# FPGA_Config.net
KiCad netlist of a schematic drawn in Altium Designer
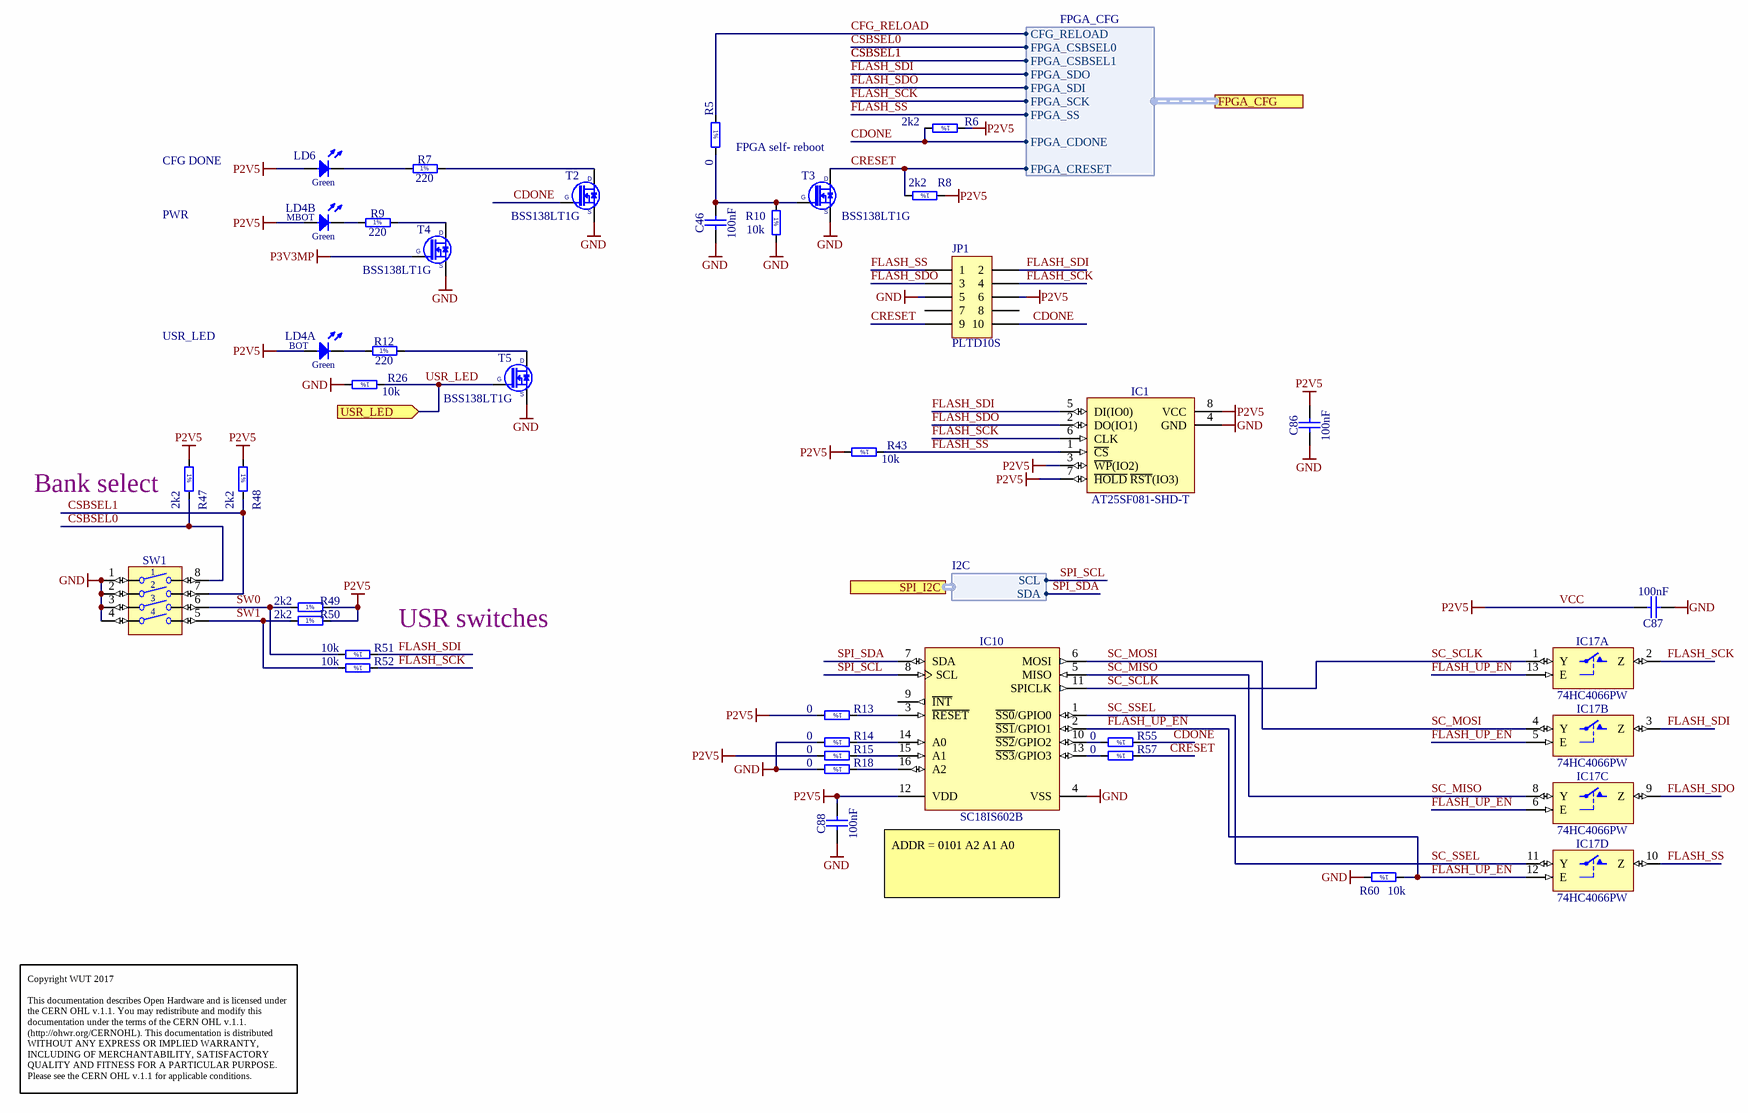
[diagram p0: FPGA_Config.SchDoc]

(export (version "E")
  (design (tool "Eeschema 10.0.6"))
  (components
    (comp (ref "C46")
      (value "100nF")
      (footprint "CAPC1005X55N")
      (description "Non-polarised capacitor")
      (fields
        (field (name "PART NUMBER") "CC0402_100NF_16V_10%_X5R")
        (field (name "VOLTAGE") "16V")
        (field (name "AUTHOR") "CERN DEM JLC")
      )
      (libsource (lib "Capacitors") (part "Capacitor - non polarized"))
    )
    (comp (ref "C86")
      (value "100nF")
      (footprint "CAPC1005X55N")
      (description "Non-polarised capacitor")
      (fields
        (field (name "PART NUMBER") "CC0402_100NF_16V_10%_X5R")
        (field (name "VOLTAGE") "16V")
        (field (name "AUTHOR") "CERN DEM JLC")
      )
      (libsource (lib "Capacitors") (part "Capacitor - non polarized"))
    )
    (comp (ref "C87")
      (value "100nF")
      (footprint "CAPC1005X55N")
      (description "Non-polarised capacitor")
      (fields
        (field (name "PART NUMBER") "CC0402_100NF_16V_10%_X5R")
        (field (name "VOLTAGE") "16V")
        (field (name "AUTHOR") "CERN DEM JLC")
      )
      (libsource (lib "Capacitors") (part "Capacitor - non polarized"))
    )
    (comp (ref "C88")
      (value "100nF")
      (footprint "CAPC1005X55N")
      (description "Non-polarised capacitor")
      (fields
        (field (name "PART NUMBER") "CC0402_100NF_16V_10%_X5R")
        (field (name "VOLTAGE") "16V")
        (field (name "AUTHOR") "CERN DEM JLC")
      )
      (libsource (lib "Capacitors") (part "Capacitor - non polarized"))
    )
    (comp (ref "IC1")
      (value "AT25SF081-SHD-T")
      (footprint "SOIC127P790X216-8N")
      (description "8M-bit Serial Flash Memory with uniform 4KB sectors and Dual/Quad SPI and QPI")
      (fields (field (name "MANUFACTURER") "ADESTO") (field (name "AUTHOR") "GK"))
      (libsource (lib "LIBRARY_SCH") (part "MEM_AT25SF081-SHD-T"))
    )
    (comp (ref "IC10")
      (value "SC18IS602B")
      (footprint "SOP65P640X110-16N")
      (description "I2C-bus to SPI bridge")
      (fields (field (name "MANUFACTURER") "NXP SEMICONDUCTORS") (field (name "AUTHOR") "CERN DEM MR"))
      (libsource (lib "ICs And Semiconductors") (part "SC18IS602B"))
    )
    (comp (ref "IC17")
      (value "74HC4066PW")
      (footprint "SOP65P640X110-14N")
      (fields (field (name "MANUFACTURER") "NXP SEMICONDUCTORS") (field (name "AUTHOR") "CERN DEM JLC"))
      (libsource (lib "ICs And Semiconductors") (part "4066"))
    )
    (comp (ref "JP1")
      (value "PLTD10S")
      (footprint "PLTD10S")
      (description "Goldpin 2.54mm, male header")
      (libsource (lib "LIBRARY_SCH") (part "CON_2x5 2.54 male SMT"))
    )
    (comp (ref "LD4")
      (value "Green/Green/HeRed/HeRed")
      (footprint "LED_BIVAR_H485CHHGGDL")
      (description "LED x4 G-1C2A-BOT_G-3C4A_H-5C6A_H-7C8A-TOP")
      (fields
        (field (name "PART NUMBER") "LED_BIVAR_H485CHHGGDL")
        (field (name "MANUFACTURER") "BIVAR")
        (field (name "AUTHOR") "CERN DEM BC")
      )
      (libsource (lib "ICs And Semiconductors") (part "LED x4 G-1C2A-BOT_G-3C4A_H-5C6A_H-7C8A-TOP"))
    )
    (comp (ref "LD6")
      (value "Green")
      (footprint "LED_KINGBRIGHT_KPH-1608CGCK")
      (description "LED Green 1C 2A")
      (fields
        (field (name "PART NUMBER") "LED_KINGBRIGHT_KPH-1608CGCK")
        (field (name "MANUFACTURER") "KINGBRIGHT")
        (field (name "AUTHOR") "CERN DEM JLC")
      )
      (libsource (lib "ICs And Semiconductors") (part "LED Green 1C 2A"))
    )
    (comp (ref "R5")
      (value "0")
      (footprint "RESC1608X55N")
      (description "Resistor - 1%")
      (fields
        (field (name "PART NUMBER") "R0603_0R_JUMPER")
        (field (name "MANUFACTURER") "GENERIC")
        (field (name "AUTHOR") "CERN DEM JLC")
      )
      (libsource (lib "Resistors") (part "Resistor - 1%"))
    )
    (comp (ref "R6")
      (value "2k2")
      (footprint "RESC1005X40N")
      (description "Resistor - 1%")
      (fields
        (field (name "PART NUMBER") "R0402_2K2_1%_0.0625W_100PPM")
        (field (name "POWER") "0.0625W")
        (field (name "AUTHOR") "CERN DEM JLC")
      )
      (libsource (lib "Resistors") (part "Resistor - 1%"))
    )
    (comp (ref "R7")
      (value "220")
      (footprint "RESC1608X55N")
      (description "Resistor - 1%")
      (fields
        (field (name "PART NUMBER") "R0603_220R_1%_0.1W_100PPM")
        (field (name "POWER") "0.1W")
        (field (name "AUTHOR") "CERN DEM JLC")
      )
      (libsource (lib "Resistors") (part "Resistor - 1%"))
    )
    (comp (ref "R8")
      (value "2k2")
      (footprint "RESC1005X40N")
      (description "Resistor - 1%")
      (fields
        (field (name "PART NUMBER") "R0402_2K2_1%_0.0625W_100PPM")
        (field (name "POWER") "0.0625W")
        (field (name "AUTHOR") "CERN DEM JLC")
      )
      (libsource (lib "Resistors") (part "Resistor - 1%"))
    )
    (comp (ref "R9")
      (value "220")
      (footprint "RESC1608X55N")
      (description "Resistor - 1%")
      (fields
        (field (name "PART NUMBER") "R0603_220R_1%_0.1W_100PPM")
        (field (name "POWER") "0.1W")
        (field (name "AUTHOR") "CERN DEM JLC")
      )
      (libsource (lib "Resistors") (part "Resistor - 1%"))
    )
    (comp (ref "R10")
      (value "10k")
      (footprint "RESC1005X40N")
      (description "Resistor - 1%")
      (fields
        (field (name "PART NUMBER") "R0402_10K_1%_0.0625W_100PPM")
        (field (name "POWER") "0.0625W")
        (field (name "AUTHOR") "CERN DEM JLC")
      )
      (libsource (lib "Resistors") (part "Resistor - 1%"))
    )
    (comp (ref "R12")
      (value "220")
      (footprint "RESC1608X55N")
      (description "Resistor - 1%")
      (fields
        (field (name "PART NUMBER") "R0603_220R_1%_0.1W_100PPM")
        (field (name "POWER") "0.1W")
        (field (name "AUTHOR") "CERN DEM JLC")
      )
      (libsource (lib "Resistors") (part "Resistor - 1%"))
    )
    (comp (ref "R13")
      (value "0")
      (footprint "RESC1608X55N")
      (description "Resistor - 1%")
      (fields
        (field (name "PART NUMBER") "R0603_0R_JUMPER")
        (field (name "MANUFACTURER") "GENERIC")
        (field (name "AUTHOR") "CERN DEM JLC")
      )
      (libsource (lib "Resistors") (part "Resistor - 1%"))
    )
    (comp (ref "R14")
      (value "0")
      (footprint "RESC1608X55N")
      (description "Resistor - 1%")
      (fields
        (field (name "PART NUMBER") "R0603_0R_JUMPER")
        (field (name "MANUFACTURER") "GENERIC")
        (field (name "AUTHOR") "CERN DEM JLC")
      )
      (libsource (lib "Resistors") (part "Resistor - 1%"))
    )
    (comp (ref "R15")
      (value "0")
      (footprint "RESC1608X55N")
      (description "Resistor - 1%")
      (fields
        (field (name "PART NUMBER") "R0603_0R_JUMPER")
        (field (name "MANUFACTURER") "GENERIC")
        (field (name "AUTHOR") "CERN DEM JLC")
      )
      (libsource (lib "Resistors") (part "Resistor - 1%"))
    )
    (comp (ref "R18")
      (value "0")
      (footprint "RESC1608X55N")
      (description "Resistor - 1%")
      (fields
        (field (name "PART NUMBER") "R0603_0R_JUMPER")
        (field (name "MANUFACTURER") "GENERIC")
        (field (name "AUTHOR") "CERN DEM JLC")
      )
      (libsource (lib "Resistors") (part "Resistor - 1%"))
    )
    (comp (ref "R26")
      (value "10k")
      (footprint "RESC1005X40N")
      (description "Resistor - 1%")
      (fields
        (field (name "PART NUMBER") "R0402_10K_1%_0.0625W_100PPM")
        (field (name "POWER") "0.0625W")
        (field (name "AUTHOR") "CERN DEM JLC")
      )
      (libsource (lib "Resistors") (part "Resistor - 1%"))
    )
    (comp (ref "R43")
      (value "10k")
      (footprint "RESC1005X40N")
      (description "Resistor - 1%")
      (fields
        (field (name "PART NUMBER") "R0402_10K_1%_0.0625W_100PPM")
        (field (name "POWER") "0.0625W")
        (field (name "AUTHOR") "CERN DEM JLC")
      )
      (libsource (lib "Resistors") (part "Resistor - 1%"))
    )
    (comp (ref "R47")
      (value "2k2")
      (footprint "RESC1005X40N")
      (description "Resistor - 1%")
      (fields
        (field (name "PART NUMBER") "R0402_2K2_1%_0.0625W_100PPM")
        (field (name "POWER") "0.0625W")
        (field (name "AUTHOR") "CERN DEM JLC")
      )
      (libsource (lib "Resistors") (part "Resistor - 1%"))
    )
    (comp (ref "R48")
      (value "2k2")
      (footprint "RESC1005X40N")
      (description "Resistor - 1%")
      (fields
        (field (name "PART NUMBER") "R0402_2K2_1%_0.0625W_100PPM")
        (field (name "POWER") "0.0625W")
        (field (name "AUTHOR") "CERN DEM JLC")
      )
      (libsource (lib "Resistors") (part "Resistor - 1%"))
    )
    (comp (ref "R49")
      (value "2k2")
      (footprint "RESC1005X40N")
      (description "Resistor - 1%")
      (fields
        (field (name "PART NUMBER") "R0402_2K2_1%_0.0625W_100PPM")
        (field (name "POWER") "0.0625W")
        (field (name "AUTHOR") "CERN DEM JLC")
      )
      (libsource (lib "Resistors") (part "Resistor - 1%"))
    )
    (comp (ref "R50")
      (value "2k2")
      (footprint "RESC1005X40N")
      (description "Resistor - 1%")
      (fields
        (field (name "PART NUMBER") "R0402_2K2_1%_0.0625W_100PPM")
        (field (name "POWER") "0.0625W")
        (field (name "AUTHOR") "CERN DEM JLC")
      )
      (libsource (lib "Resistors") (part "Resistor - 1%"))
    )
    (comp (ref "R51")
      (value "10k")
      (footprint "RESC1005X40N")
      (description "Resistor - 1%")
      (fields
        (field (name "PART NUMBER") "R0402_10K_1%_0.0625W_100PPM")
        (field (name "POWER") "0.0625W")
        (field (name "AUTHOR") "CERN DEM JLC")
      )
      (libsource (lib "Resistors") (part "Resistor - 1%"))
    )
    (comp (ref "R52")
      (value "10k")
      (footprint "RESC1005X40N")
      (description "Resistor - 1%")
      (fields
        (field (name "PART NUMBER") "R0402_10K_1%_0.0625W_100PPM")
        (field (name "POWER") "0.0625W")
        (field (name "AUTHOR") "CERN DEM JLC")
      )
      (libsource (lib "Resistors") (part "Resistor - 1%"))
    )
    (comp (ref "R55")
      (value "0")
      (footprint "RESC1608X55N")
      (description "Resistor - 1%")
      (fields
        (field (name "PART NUMBER") "R0603_0R_JUMPER")
        (field (name "MANUFACTURER") "GENERIC")
        (field (name "AUTHOR") "CERN DEM JLC")
      )
      (libsource (lib "Resistors") (part "Resistor - 1%"))
    )
    (comp (ref "R57")
      (value "0")
      (footprint "RESC1608X55N")
      (description "Resistor - 1%")
      (fields
        (field (name "PART NUMBER") "R0603_0R_JUMPER")
        (field (name "MANUFACTURER") "GENERIC")
        (field (name "AUTHOR") "CERN DEM JLC")
      )
      (libsource (lib "Resistors") (part "Resistor - 1%"))
    )
    (comp (ref "R60")
      (value "10k")
      (footprint "RESC1005X40N")
      (description "Resistor - 1%")
      (fields
        (field (name "PART NUMBER") "R0402_10K_1%_0.0625W_100PPM")
        (field (name "POWER") "0.0625W")
        (field (name "AUTHOR") "CERN DEM JLC")
      )
      (libsource (lib "Resistors") (part "Resistor - 1%"))
    )
    (comp (ref "SW1")
      (value "Switch")
      (footprint "SW_TYCO_1571983-4")
      (description "4 Ways SPST DIP Switch")
      (fields
        (field (name "PART NUMBER") "SW_TYCO_1571983-4")
        (field (name "MANUFACTURER") "TYCO")
        (field (name "AUTHOR") "CERN DEM JLC")
      )
      (libsource (lib "Eletro-mechanical") (part "SW 4x SPST DIP Switch"))
    )
    (comp (ref "T2")
      (value "BSS138LT1G")
      (footprint "SOT95P240X110-3N")
      (description "N-CHANNEL MOSFET WITH DIODE")
      (fields (field (name "MANUFACTURER") "ON SEMICONDUCTOR") (field (name "AUTHOR") "CERN DEM JLC"))
      (libsource (lib "ICs And Semiconductors") (part "N-MOSFET-D 1G 2S 3D"))
    )
    (comp (ref "T3")
      (value "BSS138LT1G")
      (footprint "SOT95P240X110-3N")
      (description "N-CHANNEL MOSFET WITH DIODE")
      (fields (field (name "MANUFACTURER") "ON SEMICONDUCTOR") (field (name "AUTHOR") "CERN DEM JLC"))
      (libsource (lib "ICs And Semiconductors") (part "N-MOSFET-D 1G 2S 3D"))
    )
    (comp (ref "T4")
      (value "BSS138LT1G")
      (footprint "SOT95P240X110-3N")
      (description "N-CHANNEL MOSFET WITH DIODE")
      (fields (field (name "MANUFACTURER") "ON SEMICONDUCTOR") (field (name "AUTHOR") "CERN DEM JLC"))
      (libsource (lib "ICs And Semiconductors") (part "N-MOSFET-D 1G 2S 3D"))
    )
    (comp (ref "T5")
      (value "BSS138LT1G")
      (footprint "SOT95P240X110-3N")
      (description "N-CHANNEL MOSFET WITH DIODE")
      (fields (field (name "MANUFACTURER") "ON SEMICONDUCTOR") (field (name "AUTHOR") "CERN DEM JLC"))
      (libsource (lib "ICs And Semiconductors") (part "N-MOSFET-D 1G 2S 3D"))
    )
  )
  (nets
    (net (code "3") (name "/CDONE") (class "Default")
      (node (ref "JP1") (pin "10") (pinfunction "10_10") (pintype "passive"))
      (node (ref "R55") (pin "1") (pinfunction "1_1") (pintype "passive"))
      (node (ref "R6") (pin "2") (pinfunction "2_2") (pintype "passive"))
      (node (ref "T2") (pin "1") (pinfunction "G_1") (pintype "passive"))
    )
    (net (code "4") (name "/CFG_RELOAD") (class "Default")
      (node (ref "R5") (pin "1") (pinfunction "1_1") (pintype "passive"))
    )
    (net (code "5") (name "/CRESET") (class "Default")
      (node (ref "JP1") (pin "9") (pinfunction "9_9") (pintype "passive"))
      (node (ref "R57") (pin "1") (pinfunction "1_1") (pintype "passive"))
      (node (ref "R8") (pin "2") (pinfunction "2_2") (pintype "passive"))
      (node (ref "T3") (pin "3") (pinfunction "D_3") (pintype "passive"))
    )
    (net (code "6") (name "/CSBSEL0") (class "Default")
      (node (ref "R47") (pin "2") (pinfunction "2_2") (pintype "passive"))
      (node (ref "SW1") (pin "8") (pinfunction "8_8") (pintype "bidirectional"))
    )
    (net (code "7") (name "/CSBSEL1") (class "Default")
      (node (ref "R48") (pin "2") (pinfunction "2_2") (pintype "passive"))
      (node (ref "SW1") (pin "7") (pinfunction "7_7") (pintype "bidirectional"))
    )
    (net (code "8") (name "/FLASH_SCK") (class "Default")
      (node (ref "IC1") (pin "6") (pinfunction "CLK_6") (pintype "input"))
      (node (ref "IC17") (pin "2") (pinfunction "Z_2") (pintype "bidirectional"))
      (node (ref "JP1") (pin "4") (pinfunction "4_4") (pintype "passive"))
      (node (ref "R52") (pin "1") (pinfunction "1_1") (pintype "passive"))
    )
    (net (code "9") (name "/FLASH_SDI") (class "Default")
      (node (ref "IC1") (pin "5") (pinfunction "DI(IO0)_5") (pintype "bidirectional"))
      (node (ref "IC17") (pin "3") (pinfunction "Z_3") (pintype "bidirectional"))
      (node (ref "JP1") (pin "2") (pinfunction "2_2") (pintype "passive"))
      (node (ref "R51") (pin "1") (pinfunction "1_1") (pintype "passive"))
    )
    (net (code "10") (name "/FLASH_SDO") (class "Default")
      (node (ref "IC1") (pin "2") (pinfunction "DO(IO1)_2") (pintype "bidirectional"))
      (node (ref "IC17") (pin "9") (pinfunction "Z_9") (pintype "bidirectional"))
      (node (ref "JP1") (pin "3") (pinfunction "3_3") (pintype "passive"))
    )
    (net (code "11") (name "/FLASH_SS") (class "Default")
      (node (ref "IC1") (pin "1") (pinfunction "~{CS}_1") (pintype "input"))
      (node (ref "IC17") (pin "10") (pinfunction "Z_10") (pintype "bidirectional"))
      (node (ref "JP1") (pin "1") (pinfunction "1_1") (pintype "passive"))
      (node (ref "R43") (pin "1") (pinfunction "1_1") (pintype "passive"))
    )
    (net (code "12") (name "/FLASH_UP_EN") (class "Default")
      (node (ref "IC10") (pin "2") (pinfunction "~{SS1}/GPIO1_2") (pintype "bidirectional"))
      (node (ref "IC17") (pin "12") (pinfunction "E_12") (pintype "input"))
      (node (ref "IC17") (pin "13") (pinfunction "E_13") (pintype "input"))
      (node (ref "IC17") (pin "5") (pinfunction "E_5") (pintype "input"))
      (node (ref "IC17") (pin "6") (pinfunction "E_6") (pintype "input"))
      (node (ref "R60") (pin "1") (pinfunction "1_1") (pintype "passive"))
    )
    (net (code "13") (name "/SC_MISO") (class "Default")
      (node (ref "IC10") (pin "5") (pinfunction "MISO_5") (pintype "input"))
      (node (ref "IC17") (pin "8") (pinfunction "Y_8") (pintype "bidirectional"))
    )
    (net (code "14") (name "/SC_MOSI") (class "Default")
      (node (ref "IC10") (pin "6") (pinfunction "MOSI_6") (pintype "output"))
      (node (ref "IC17") (pin "4") (pinfunction "Y_4") (pintype "bidirectional"))
    )
    (net (code "15") (name "/SC_SCLK") (class "Default")
      (node (ref "IC10") (pin "11") (pinfunction "SPICLK_11") (pintype "output"))
      (node (ref "IC17") (pin "1") (pinfunction "Y_1") (pintype "bidirectional"))
    )
    (net (code "16") (name "/SC_SSEL") (class "Default")
      (node (ref "IC10") (pin "1") (pinfunction "~{SS0}/GPIO0_1") (pintype "bidirectional"))
      (node (ref "IC17") (pin "11") (pinfunction "Y_11") (pintype "bidirectional"))
    )
    (net (code "17") (name "/SPI_SCL") (class "Default")
      (node (ref "IC10") (pin "8") (pinfunction "SCL_8") (pintype "input"))
    )
    (net (code "18") (name "/SPI_SDA") (class "Default")
      (node (ref "IC10") (pin "7") (pinfunction "SDA_7") (pintype "bidirectional"))
    )
    (net (code "19") (name "/SW0") (class "Default")
      (node (ref "R49") (pin "1") (pinfunction "1_1") (pintype "passive"))
      (node (ref "R51") (pin "2") (pinfunction "2_2") (pintype "passive"))
      (node (ref "SW1") (pin "6") (pinfunction "6_6") (pintype "bidirectional"))
    )
    (net (code "20") (name "/SW1") (class "Default")
      (node (ref "R50") (pin "1") (pinfunction "1_1") (pintype "passive"))
      (node (ref "R52") (pin "2") (pinfunction "2_2") (pintype "passive"))
      (node (ref "SW1") (pin "5") (pinfunction "5_5") (pintype "bidirectional"))
    )
    (net (code "21") (name "/USR_LED") (class "Default")
      (node (ref "R26") (pin "1") (pinfunction "1_1") (pintype "passive"))
      (node (ref "T5") (pin "1") (pinfunction "G_1") (pintype "passive"))
    )
    (net (code "24") (name "GND") (class "Default")
      (node (ref "C46") (pin "1") (pinfunction "1_1") (pintype "passive"))
      (node (ref "C86") (pin "1") (pinfunction "1_1") (pintype "passive"))
      (node (ref "C87") (pin "1") (pinfunction "1_1") (pintype "passive"))
      (node (ref "C88") (pin "1") (pinfunction "1_1") (pintype "passive"))
      (node (ref "IC1") (pin "4") (pinfunction "GND_4") (pintype "power_in"))
      (node (ref "IC10") (pin "4") (pinfunction "VSS_4") (pintype "power_in"))
      (node (ref "IC17") (pin "7") (pinfunction "GND_7") (pintype "power_in"))
      (node (ref "JP1") (pin "5") (pinfunction "5_5") (pintype "passive"))
      (node (ref "R10") (pin "2") (pinfunction "2_2") (pintype "passive"))
      (node (ref "R14") (pin "2") (pinfunction "2_2") (pintype "passive"))
      (node (ref "R18") (pin "2") (pinfunction "2_2") (pintype "passive"))
      (node (ref "R26") (pin "2") (pinfunction "2_2") (pintype "passive"))
      (node (ref "R60") (pin "2") (pinfunction "2_2") (pintype "passive"))
      (node (ref "SW1") (pin "1") (pinfunction "1_1") (pintype "bidirectional"))
      (node (ref "SW1") (pin "2") (pinfunction "2_2") (pintype "bidirectional"))
      (node (ref "SW1") (pin "3") (pinfunction "3_3") (pintype "bidirectional"))
      (node (ref "SW1") (pin "4") (pinfunction "4_4") (pintype "bidirectional"))
      (node (ref "T2") (pin "2") (pinfunction "S_2") (pintype "passive"))
      (node (ref "T3") (pin "2") (pinfunction "S_2") (pintype "passive"))
      (node (ref "T4") (pin "2") (pinfunction "S_2") (pintype "passive"))
      (node (ref "T5") (pin "2") (pinfunction "S_2") (pintype "passive"))
    )
    (net (code "25") (name "Net-(IC10-A0)") (class "Default")
      (node (ref "IC10") (pin "14") (pinfunction "A0_14") (pintype "input"))
      (node (ref "R14") (pin "1") (pinfunction "1_1") (pintype "passive"))
    )
    (net (code "26") (name "Net-(IC10-A1)") (class "Default")
      (node (ref "IC10") (pin "15") (pinfunction "A1_15") (pintype "input"))
      (node (ref "R15") (pin "1") (pinfunction "1_1") (pintype "passive"))
    )
    (net (code "27") (name "Net-(IC10-A2)") (class "Default")
      (node (ref "IC10") (pin "16") (pinfunction "A2_16") (pintype "bidirectional"))
      (node (ref "R18") (pin "1") (pinfunction "1_1") (pintype "passive"))
    )
    (net (code "28") (name "Net-(IC10-~{RESET})") (class "Default")
      (node (ref "IC10") (pin "3") (pinfunction "~{RESET}_3") (pintype "input"))
      (node (ref "R13") (pin "1") (pinfunction "1_1") (pintype "passive"))
    )
    (net (code "29") (name "Net-(IC10-~{SS2}{slash}GPIO2)") (class "Default")
      (node (ref "IC10") (pin "10") (pinfunction "~{SS2}/GPIO2_10") (pintype "bidirectional"))
      (node (ref "R55") (pin "2") (pinfunction "2_2") (pintype "passive"))
    )
    (net (code "30") (name "Net-(IC10-~{SS3}{slash}GPIO3)") (class "Default")
      (node (ref "IC10") (pin "13") (pinfunction "~{SS3}/GPIO3_13") (pintype "bidirectional"))
      (node (ref "R57") (pin "2") (pinfunction "2_2") (pintype "passive"))
    )
    (net (code "31") (name "Net-(LD4A-C)") (class "Default")
      (node (ref "LD4") (pin "1") (pinfunction "C_1") (pintype "passive"))
      (node (ref "R12") (pin "1") (pinfunction "1_1") (pintype "passive"))
    )
    (net (code "32") (name "Net-(LD4B-C)") (class "Default")
      (node (ref "LD4") (pin "3") (pinfunction "C_3") (pintype "passive"))
      (node (ref "R9") (pin "1") (pinfunction "1_1") (pintype "passive"))
    )
    (net (code "33") (name "Net-(LD6-C)") (class "Default")
      (node (ref "LD6") (pin "1") (pinfunction "C_1") (pintype "passive"))
      (node (ref "R7") (pin "1") (pinfunction "1_1") (pintype "passive"))
    )
    (net (code "34") (name "Net-(T2-D)") (class "Default")
      (node (ref "R7") (pin "2") (pinfunction "2_2") (pintype "passive"))
      (node (ref "T2") (pin "3") (pinfunction "D_3") (pintype "passive"))
    )
    (net (code "35") (name "Net-(T3-G)") (class "Default")
      (node (ref "C46") (pin "2") (pinfunction "2_2") (pintype "passive"))
      (node (ref "R10") (pin "1") (pinfunction "1_1") (pintype "passive"))
      (node (ref "R5") (pin "2") (pinfunction "2_2") (pintype "passive"))
      (node (ref "T3") (pin "1") (pinfunction "G_1") (pintype "passive"))
    )
    (net (code "36") (name "Net-(T4-D)") (class "Default")
      (node (ref "R9") (pin "2") (pinfunction "2_2") (pintype "passive"))
      (node (ref "T4") (pin "3") (pinfunction "D_3") (pintype "passive"))
    )
    (net (code "37") (name "Net-(T5-D)") (class "Default")
      (node (ref "R12") (pin "2") (pinfunction "2_2") (pintype "passive"))
      (node (ref "T5") (pin "3") (pinfunction "D_3") (pintype "passive"))
    )
    (net (code "38") (name "P2V5") (class "Default")
      (node (ref "C86") (pin "2") (pinfunction "2_2") (pintype "passive"))
      (node (ref "C87") (pin "2") (pinfunction "2_2") (pintype "passive"))
      (node (ref "C88") (pin "2") (pinfunction "2_2") (pintype "passive"))
      (node (ref "IC1") (pin "3") (pinfunction "~{WP}(IO2)_3") (pintype "bidirectional"))
      (node (ref "IC1") (pin "7") (pinfunction "~{HOLD}_~{RST}(IO3)_7") (pintype "bidirectional"))
      (node (ref "IC1") (pin "8") (pinfunction "VCC_8") (pintype "power_in"))
      (node (ref "IC10") (pin "12") (pinfunction "VDD_12") (pintype "power_in"))
      (node (ref "IC17") (pin "14") (pinfunction "VCC_14") (pintype "power_in"))
      (node (ref "JP1") (pin "6") (pinfunction "6_6") (pintype "passive"))
      (node (ref "LD4") (pin "2") (pinfunction "A_2") (pintype "passive"))
      (node (ref "LD4") (pin "4") (pinfunction "A_4") (pintype "passive"))
      (node (ref "LD6") (pin "2") (pinfunction "A_2") (pintype "passive"))
      (node (ref "R13") (pin "2") (pinfunction "2_2") (pintype "passive"))
      (node (ref "R15") (pin "2") (pinfunction "2_2") (pintype "passive"))
      (node (ref "R43") (pin "2") (pinfunction "2_2") (pintype "passive"))
      (node (ref "R47") (pin "1") (pinfunction "1_1") (pintype "passive"))
      (node (ref "R48") (pin "1") (pinfunction "1_1") (pintype "passive"))
      (node (ref "R49") (pin "2") (pinfunction "2_2") (pintype "passive"))
      (node (ref "R50") (pin "2") (pinfunction "2_2") (pintype "passive"))
      (node (ref "R6") (pin "1") (pinfunction "1_1") (pintype "passive"))
      (node (ref "R8") (pin "1") (pinfunction "1_1") (pintype "passive"))
    )
    (net (code "39") (name "P3V3MP") (class "Default")
      (node (ref "T4") (pin "1") (pinfunction "G_1") (pintype "passive"))
    )
    (net (code "40") (name "unconnected-(IC10-~{INT}-Pad9)") (class "Default")
      (node (ref "IC10") (pin "9") (pinfunction "~{INT}_9") (pintype "output"))
    )
    (net (code "41") (name "unconnected-(JP1-Pad7)") (class "Default")
      (node (ref "JP1") (pin "7") (pinfunction "7_7") (pintype "passive"))
    )
    (net (code "42") (name "unconnected-(JP1-Pad8)") (class "Default")
      (node (ref "JP1") (pin "8") (pinfunction "8_8") (pintype "passive"))
    )
  )
)
